# LIA.net
KiCad netlist of a schematic drawn in Altium Designer
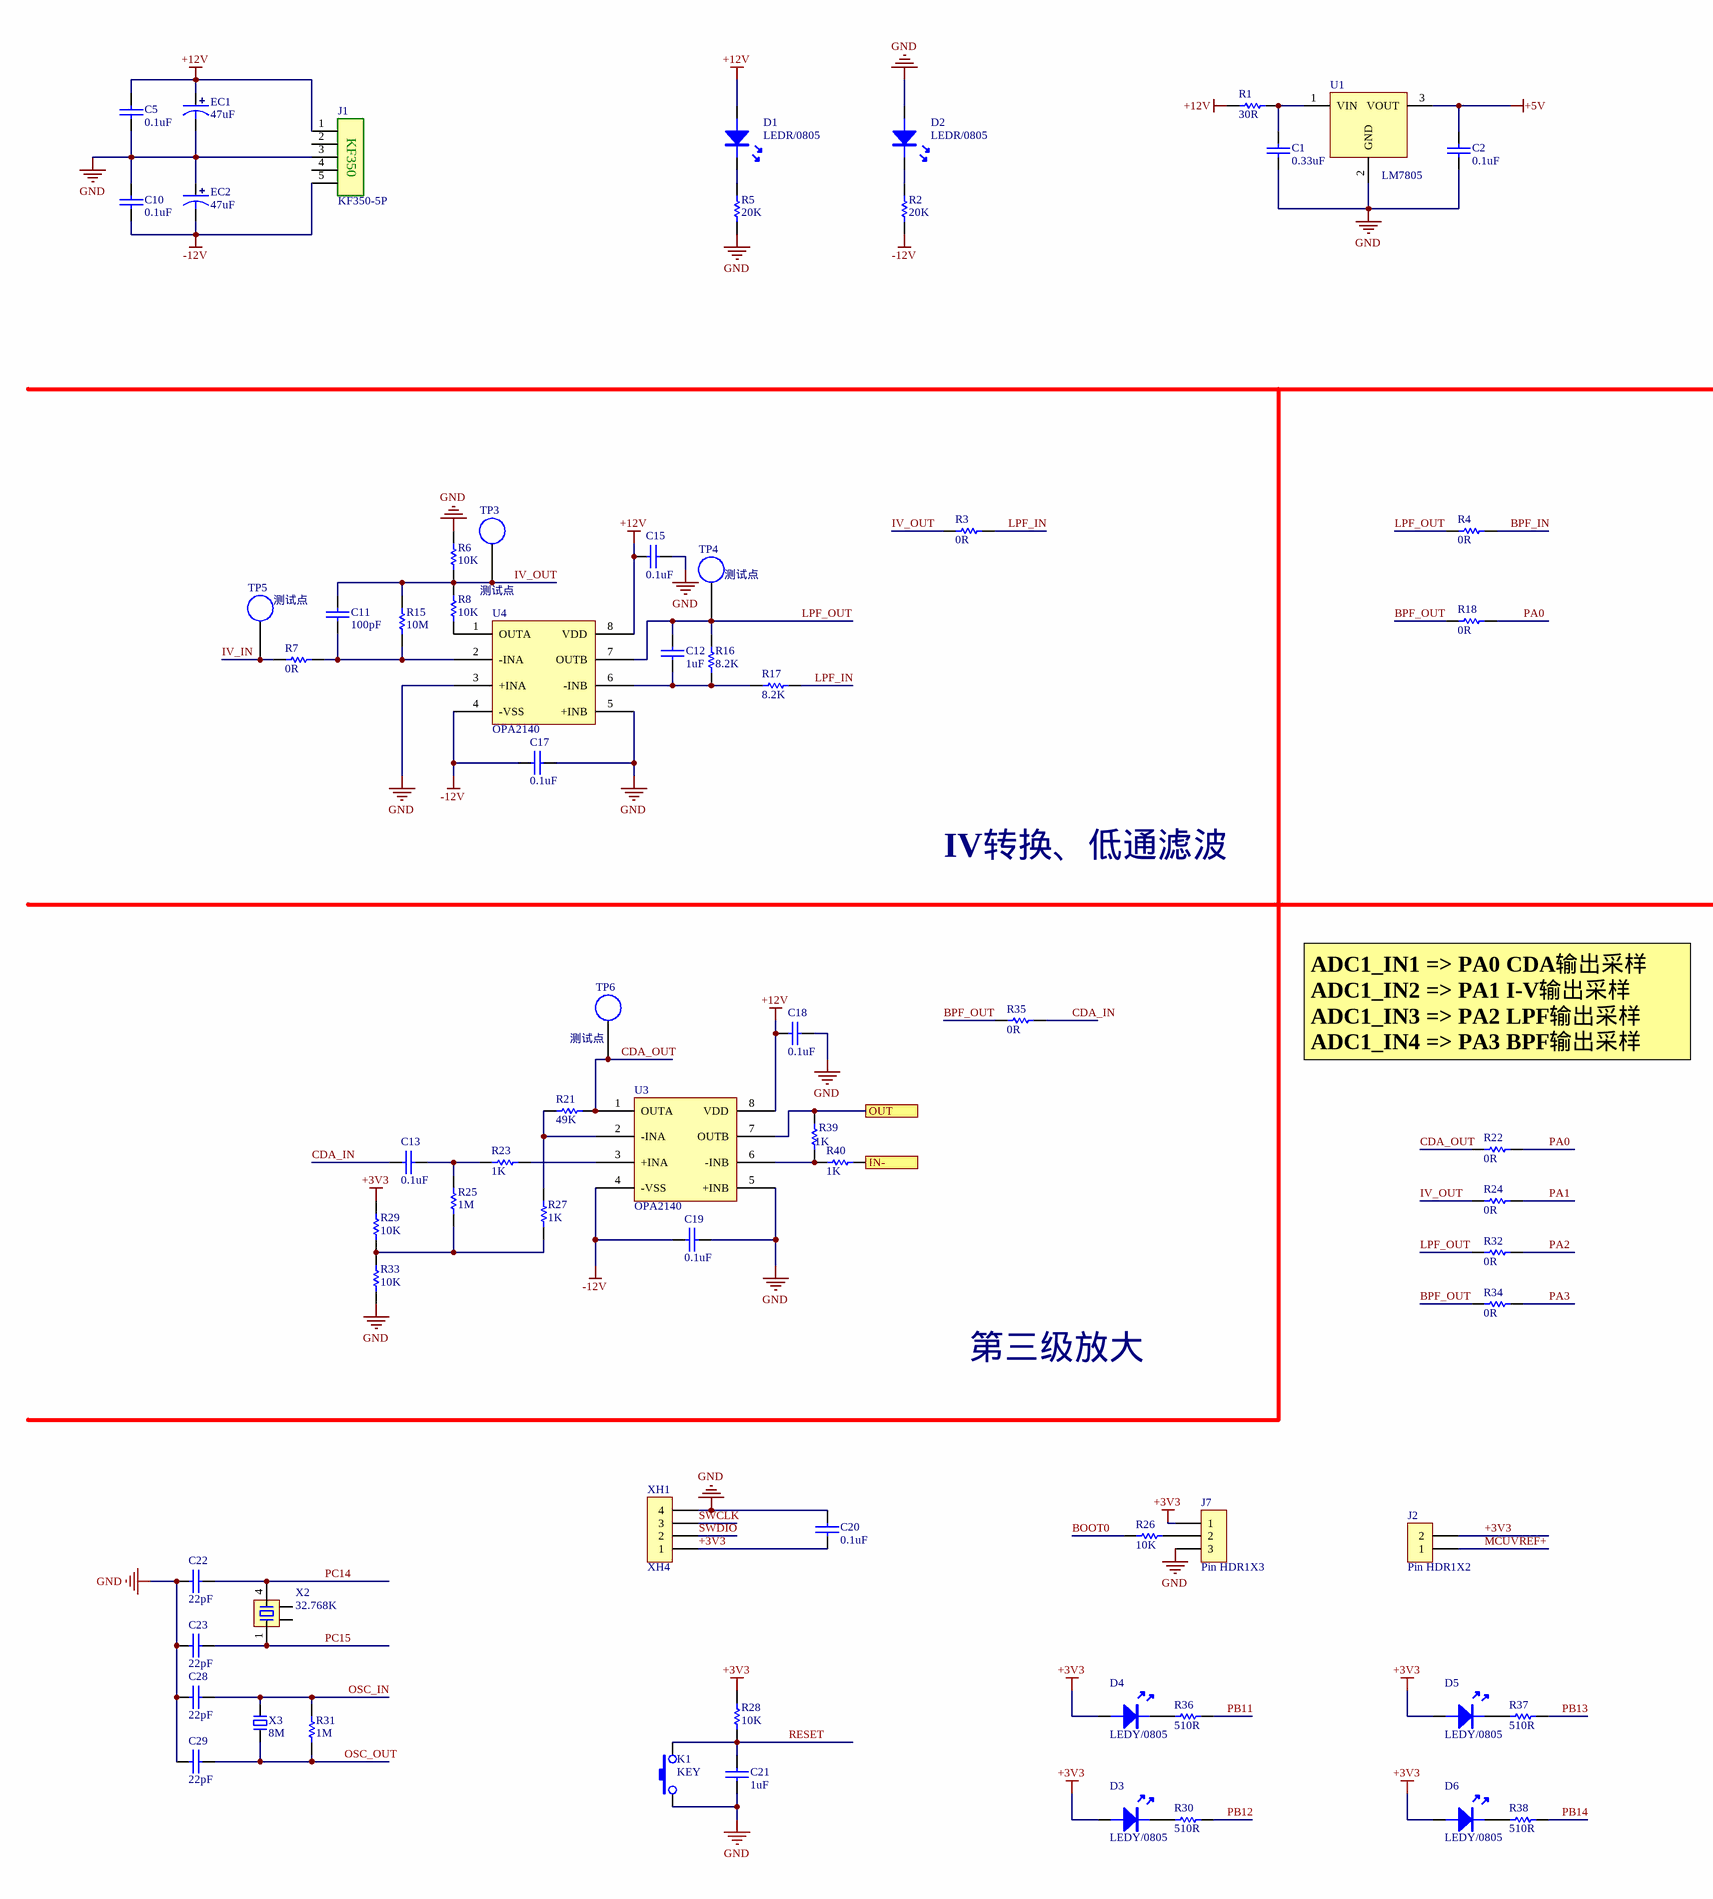
[diagram p0: LIA.SchDoc, left]
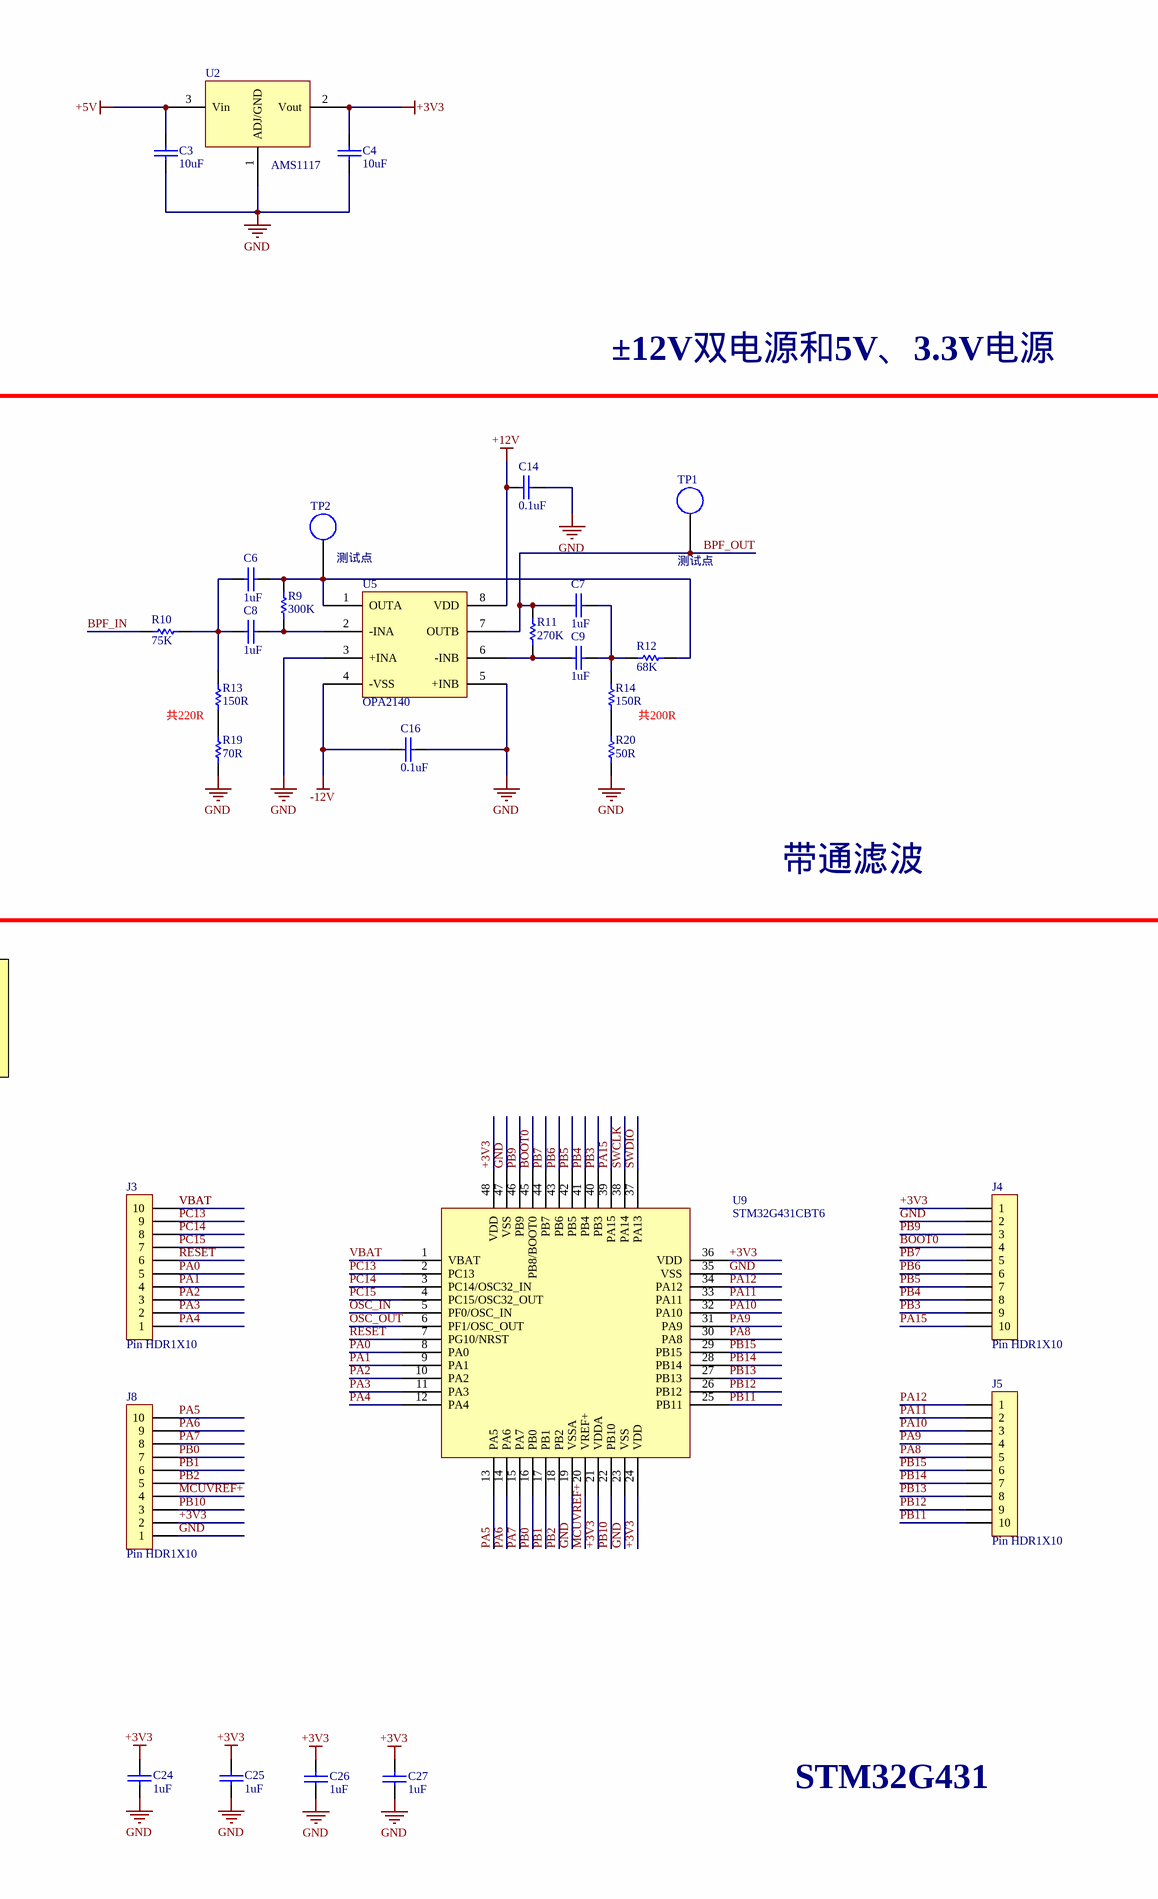
[diagram p1: LIA.SchDoc, right]

(export (version "E")
  (design (tool "Eeschema 10.0.6"))
  (components
    (comp (ref "C1")
      (value "0.33uF")
      (footprint "0603C")
      (description "无极性电容")
      (libsource (lib "电容") (part "CAP"))
    )
    (comp (ref "C2")
      (value "0.1uF")
      (footprint "0603C")
      (description "无极性电容")
      (libsource (lib "电容") (part "CAP"))
    )
    (comp (ref "C3")
      (value "10uF")
      (footprint "0603C")
      (description "无极性电容")
      (libsource (lib "电容") (part "CAP"))
    )
    (comp (ref "C4")
      (value "10uF")
      (footprint "0603C")
      (description "无极性电容")
      (libsource (lib "电容") (part "CAP"))
    )
    (comp (ref "C5")
      (value "0.1uF")
      (footprint "0603C")
      (description "无极性电容")
      (libsource (lib "电容") (part "CAP"))
    )
    (comp (ref "C6")
      (value "1uF")
      (footprint "DIP-7")
      (description "无极性电容")
      (libsource (lib "电容") (part "CAP"))
    )
    (comp (ref "C7")
      (value "1uF")
      (footprint "DIP-7")
      (description "无极性电容")
      (libsource (lib "电容") (part "CAP"))
    )
    (comp (ref "C8")
      (value "1uF")
      (footprint "DIP-7")
      (description "无极性电容")
      (libsource (lib "电容") (part "CAP"))
    )
    (comp (ref "C9")
      (value "1uF")
      (footprint "DIP-7")
      (description "无极性电容")
      (libsource (lib "电容") (part "CAP"))
    )
    (comp (ref "C10")
      (value "0.1uF")
      (footprint "0603C")
      (description "无极性电容")
      (libsource (lib "电容") (part "CAP"))
    )
    (comp (ref "C11")
      (value "100pF")
      (footprint "0603C")
      (description "无极性电容")
      (libsource (lib "电容") (part "CAP"))
    )
    (comp (ref "C12")
      (value "1uF")
      (footprint "0603C")
      (description "无极性电容")
      (libsource (lib "电容") (part "CAP"))
    )
    (comp (ref "C13")
      (value "0.1uF")
      (footprint "0603C")
      (description "无极性电容")
      (libsource (lib "电容") (part "CAP"))
    )
    (comp (ref "C14")
      (value "0.1uF")
      (footprint "0603C")
      (description "无极性电容")
      (libsource (lib "电容") (part "CAP"))
    )
    (comp (ref "C15")
      (value "0.1uF")
      (footprint "0603C")
      (description "无极性电容")
      (libsource (lib "电容") (part "CAP"))
    )
    (comp (ref "C16")
      (value "0.1uF")
      (footprint "0603C")
      (description "无极性电容")
      (libsource (lib "电容") (part "CAP"))
    )
    (comp (ref "C17")
      (value "0.1uF")
      (footprint "0603C")
      (description "无极性电容")
      (libsource (lib "电容") (part "CAP"))
    )
    (comp (ref "C18")
      (value "0.1uF")
      (footprint "0603C")
      (description "无极性电容")
      (libsource (lib "电容") (part "CAP"))
    )
    (comp (ref "C19")
      (value "0.1uF")
      (footprint "0603C")
      (description "无极性电容")
      (libsource (lib "电容") (part "CAP"))
    )
    (comp (ref "C20")
      (value "0.1uF")
      (footprint "0603C")
      (description "无极性电容")
      (libsource (lib "电容") (part "CAP"))
    )
    (comp (ref "C21")
      (value "1uF")
      (footprint "0603C")
      (description "无极性电容")
      (libsource (lib "电容") (part "CAP"))
    )
    (comp (ref "C22")
      (value "22pF")
      (footprint "0603C")
      (description "无极性电容")
      (libsource (lib "电容") (part "CAP"))
    )
    (comp (ref "C23")
      (value "22pF")
      (footprint "0603C")
      (description "无极性电容")
      (libsource (lib "电容") (part "CAP"))
    )
    (comp (ref "C24")
      (value "1uF")
      (footprint "0603C")
      (description "无极性电容")
      (libsource (lib "电容") (part "CAP"))
    )
    (comp (ref "C25")
      (value "1uF")
      (footprint "0603C")
      (description "无极性电容")
      (libsource (lib "电容") (part "CAP"))
    )
    (comp (ref "C26")
      (value "1uF")
      (footprint "0603C")
      (description "无极性电容")
      (libsource (lib "电容") (part "CAP"))
    )
    (comp (ref "C27")
      (value "1uF")
      (footprint "0603C")
      (description "无极性电容")
      (libsource (lib "电容") (part "CAP"))
    )
    (comp (ref "C28")
      (value "22pF")
      (footprint "0603C")
      (description "无极性电容")
      (libsource (lib "电容") (part "CAP"))
    )
    (comp (ref "C29")
      (value "22pF")
      (footprint "0603C")
      (description "无极性电容")
      (libsource (lib "电容") (part "CAP"))
    )
    (comp (ref "D1") (value "LEDR/0805") (footprint "LED-0805R") (libsource (lib "LED") (part "LED")))
    (comp (ref "D2") (value "LEDR/0805") (footprint "LED-0805R") (libsource (lib "LED") (part "LED")))
    (comp (ref "D3") (value "LEDY/0805") (footprint "LED-0805Y") (libsource (lib "LED") (part "LED")))
    (comp (ref "D4") (value "LEDY/0805") (footprint "LED-0805Y") (libsource (lib "LED") (part "LED")))
    (comp (ref "D5") (value "LEDY/0805") (footprint "LED-0805Y") (libsource (lib "LED") (part "LED")))
    (comp (ref "D6") (value "LEDY/0805") (footprint "LED-0805Y") (libsource (lib "LED") (part "LED")))
    (comp (ref "EC1")
      (value "47uF")
      (footprint "SMD-EC5.0X5.3X5.4")
      (description "贴片电解电容")
      (libsource (lib "电容") (part "SMD_ECAP"))
    )
    (comp (ref "EC2")
      (value "47uF")
      (footprint "SMD-EC5.0X5.3X5.4")
      (description "贴片电解电容")
      (libsource (lib "电容") (part "SMD_ECAP"))
    )
    (comp (ref "J1") (value "KF350-5P") (footprint "KF350-5P") (libsource (lib "KF350") (part "KF350-5P")))
    (comp (ref "J2")
      (value "Pin HDR1X2")
      (footprint "Pin HDR1X2/2.54mm-S")
      (libsource (lib "排针") (part "Pin HDR1X2"))
    )
    (comp (ref "J3")
      (value "Pin HDR1X10")
      (footprint "Pin HDR1X10/2.54mm-S")
      (libsource (lib "") (part "Pin HDR1X10_1"))
    )
    (comp (ref "J4")
      (value "Pin HDR1X10")
      (footprint "Pin HDR1X10/2.54mm-S")
      (libsource (lib "排针") (part "Pin HDR1X10"))
    )
    (comp (ref "J5")
      (value "Pin HDR1X10")
      (footprint "Pin HDR1X10/2.54mm-S")
      (libsource (lib "排针") (part "Pin HDR1X10"))
    )
    (comp (ref "J7")
      (value "Pin HDR1X3")
      (footprint "Pin HDR1X3/2.54mm-S")
      (libsource (lib "排针") (part "Pin HDR1X3"))
    )
    (comp (ref "J8")
      (value "Pin HDR1X10")
      (footprint "Pin HDR1X10/2.54mm-S")
      (libsource (lib "") (part "Pin HDR1X10_1"))
    )
    (comp (ref "K1") (value "KEY") (footprint "SMD-3X6X2.5") (libsource (lib "轻触开关") (part "KEY")))
    (comp (ref "R1") (value "30R") (footprint "0603R") (libsource (lib "电阻") (part "RES")))
    (comp (ref "R2") (value "20K") (footprint "0603R") (libsource (lib "电阻") (part "RES")))
    (comp (ref "R3") (value "0R") (footprint "0603R") (libsource (lib "电阻") (part "RES")))
    (comp (ref "R4") (value "0R") (footprint "0603R") (libsource (lib "电阻") (part "RES")))
    (comp (ref "R5") (value "20K") (footprint "0603R") (libsource (lib "电阻") (part "RES")))
    (comp (ref "R6") (value "10K") (footprint "0603R") (libsource (lib "电阻") (part "RES")))
    (comp (ref "R7") (value "0R") (footprint "0603R") (libsource (lib "电阻") (part "RES")))
    (comp (ref "R8") (value "10K") (footprint "0603R") (libsource (lib "电阻") (part "RES")))
    (comp (ref "R9") (value "300K") (footprint "0603R") (libsource (lib "电阻") (part "RES")))
    (comp (ref "R10") (value "75K") (footprint "0603R") (libsource (lib "电阻") (part "RES")))
    (comp (ref "R11") (value "270K") (footprint "0603R") (libsource (lib "电阻") (part "RES")))
    (comp (ref "R12") (value "68K") (footprint "0603R") (libsource (lib "电阻") (part "RES")))
    (comp (ref "R13") (value "150R") (footprint "0603R") (libsource (lib "电阻") (part "RES")))
    (comp (ref "R14") (value "150R") (footprint "0603R") (libsource (lib "电阻") (part "RES")))
    (comp (ref "R15") (value "10M") (footprint "0603R") (libsource (lib "电阻") (part "RES")))
    (comp (ref "R16") (value "8.2K") (footprint "0603R") (libsource (lib "电阻") (part "RES")))
    (comp (ref "R17") (value "8.2K") (footprint "0603R") (libsource (lib "电阻") (part "RES")))
    (comp (ref "R18") (value "0R") (footprint "0603R") (libsource (lib "电阻") (part "RES")))
    (comp (ref "R19") (value "70R") (footprint "0603R") (libsource (lib "电阻") (part "RES")))
    (comp (ref "R20") (value "50R") (footprint "0603R") (libsource (lib "电阻") (part "RES")))
    (comp (ref "R21") (value "49K") (footprint "0603R") (libsource (lib "电阻") (part "RES")))
    (comp (ref "R22") (value "0R") (footprint "0603R") (libsource (lib "电阻") (part "RES")))
    (comp (ref "R23") (value "1K") (footprint "0603R") (libsource (lib "电阻") (part "RES")))
    (comp (ref "R24") (value "0R") (footprint "0603R") (libsource (lib "电阻") (part "RES")))
    (comp (ref "R25") (value "1M") (footprint "0603R") (libsource (lib "电阻") (part "RES")))
    (comp (ref "R26") (value "10K") (footprint "0603R") (libsource (lib "电阻") (part "RES")))
    (comp (ref "R27") (value "1K") (footprint "0603R") (libsource (lib "电阻") (part "RES")))
    (comp (ref "R28") (value "10K") (footprint "0603R") (libsource (lib "电阻") (part "RES")))
    (comp (ref "R29") (value "10K") (footprint "0603R") (libsource (lib "电阻") (part "RES")))
    (comp (ref "R30") (value "510R") (footprint "0603R") (libsource (lib "电阻") (part "RES")))
    (comp (ref "R31") (value "1M") (footprint "0603R") (libsource (lib "电阻") (part "RES")))
    (comp (ref "R32") (value "0R") (footprint "0603R") (libsource (lib "电阻") (part "RES")))
    (comp (ref "R33") (value "10K") (footprint "0603R") (libsource (lib "电阻") (part "RES")))
    (comp (ref "R34") (value "0R") (footprint "0603R") (libsource (lib "电阻") (part "RES")))
    (comp (ref "R35") (value "0R") (footprint "0603R") (libsource (lib "电阻") (part "RES")))
    (comp (ref "R36") (value "510R") (footprint "0603R") (libsource (lib "电阻") (part "RES")))
    (comp (ref "R37") (value "510R") (footprint "0603R") (libsource (lib "电阻") (part "RES")))
    (comp (ref "R38") (value "510R") (footprint "0603R") (libsource (lib "电阻") (part "RES")))
    (comp (ref "R39") (value "1K") (footprint "0603R") (libsource (lib "电阻") (part "RES")))
    (comp (ref "R40") (value "1K") (footprint "0603R") (libsource (lib "电阻") (part "RES")))
    (comp (ref "TP1") (value "测试点") (footprint "TP") (libsource (lib "固定柱和测试点") (part "测试点")))
    (comp (ref "TP2") (value "测试点") (footprint "TP") (libsource (lib "固定柱和测试点") (part "测试点")))
    (comp (ref "TP3") (value "测试点") (footprint "TP") (libsource (lib "固定柱和测试点") (part "测试点")))
    (comp (ref "TP4") (value "测试点") (footprint "TP") (libsource (lib "固定柱和测试点") (part "测试点")))
    (comp (ref "TP5") (value "测试点") (footprint "TP") (libsource (lib "固定柱和测试点") (part "测试点")))
    (comp (ref "TP6") (value "测试点") (footprint "TP") (libsource (lib "固定柱和测试点") (part "测试点")))
    (comp (ref "U1") (value "LM7805") (footprint "TO252") (libsource (lib "电源芯片") (part "LM7805")))
    (comp (ref "U2")
      (value "AMS1117")
      (footprint "SOT223")
      (description "三端稳压芯片")
      (libsource (lib "电源芯片") (part "AMS1117"))
    )
    (comp (ref "U3") (value "OPA2140") (footprint "SOP8") (libsource (lib "未分类IC") (part "NE5532")))
    (comp (ref "U4") (value "OPA2140") (footprint "SOP8") (libsource (lib "未分类IC") (part "NE5532")))
    (comp (ref "U5") (value "OPA2140") (footprint "SOP8") (libsource (lib "未分类IC") (part "NE5532")))
    (comp (ref "U9")
      (value "STM32G431CBT6")
      (footprint "LQFP48 7X7")
      (libsource (lib "STM32系列") (part "STM32G431CBT6"))
    )
    (comp (ref "X2")
      (value "32.768K")
      (footprint "OSC MC-306")
      (description "MC系列4脚晶振")
      (libsource (lib "晶振") (part "XTAL-MC-4P"))
    )
    (comp (ref "X3")
      (value "8M")
      (footprint "OSC HC-49S")
      (description "2脚无源脚晶振")
      (libsource (lib "晶振") (part "XTAL-2P"))
    )
    (comp (ref "XH1") (value "XH4") (footprint "XH4/2.54mm/180") (libsource (lib "XH，VH") (part "XH4")))
  )
  (nets
    (net (code "1") (name "+3V3") (class "Default")
      (node (ref "C20") (pin "1") (pinfunction "1_1") (pintype "passive"))
      (node (ref "C24") (pin "2") (pinfunction "2_2") (pintype "passive"))
      (node (ref "C25") (pin "2") (pinfunction "2_2") (pintype "passive"))
      (node (ref "C26") (pin "2") (pinfunction "2_2") (pintype "passive"))
      (node (ref "C27") (pin "2") (pinfunction "2_2") (pintype "passive"))
      (node (ref "C4") (pin "2") (pinfunction "2_2") (pintype "passive"))
      (node (ref "D3") (pin "A") (pinfunction "A_A") (pintype "passive"))
      (node (ref "D4") (pin "A") (pinfunction "A_A") (pintype "passive"))
      (node (ref "D5") (pin "A") (pinfunction "A_A") (pintype "passive"))
      (node (ref "D6") (pin "A") (pinfunction "A_A") (pintype "passive"))
      (node (ref "J2") (pin "2") (pinfunction "2_2") (pintype "passive"))
      (node (ref "J4") (pin "1") (pinfunction "1_1") (pintype "passive"))
      (node (ref "J7") (pin "1") (pinfunction "1_1") (pintype "passive"))
      (node (ref "J8") (pin "2") (pinfunction "2_2") (pintype "passive"))
      (node (ref "R28") (pin "1") (pinfunction "1_1") (pintype "passive"))
      (node (ref "R29") (pin "2") (pinfunction "2_2") (pintype "passive"))
      (node (ref "U2") (pin "2") (pinfunction "Vout_2") (pintype "passive"))
      (node (ref "U9") (pin "21") (pinfunction "VDDA_21") (pintype "passive"))
      (node (ref "U9") (pin "24") (pinfunction "VDD_24") (pintype "passive"))
      (node (ref "U9") (pin "36") (pinfunction "VDD_36") (pintype "passive"))
      (node (ref "U9") (pin "48") (pinfunction "VDD_48") (pintype "passive"))
      (node (ref "XH1") (pin "1") (pinfunction "1_1") (pintype "passive"))
    )
    (net (code "2") (name "+5V") (class "Default")
      (node (ref "C2") (pin "2") (pinfunction "2_2") (pintype "passive"))
      (node (ref "C3") (pin "2") (pinfunction "2_2") (pintype "passive"))
      (node (ref "U1") (pin "3") (pinfunction "VOUT_3") (pintype "passive"))
      (node (ref "U2") (pin "3") (pinfunction "Vin_3") (pintype "passive"))
    )
    (net (code "3") (name "+12V") (class "Default")
      (node (ref "C14") (pin "1") (pinfunction "1_1") (pintype "passive"))
      (node (ref "C15") (pin "1") (pinfunction "1_1") (pintype "passive"))
      (node (ref "C18") (pin "1") (pinfunction "1_1") (pintype "passive"))
      (node (ref "C5") (pin "2") (pinfunction "2_2") (pintype "passive"))
      (node (ref "D1") (pin "A") (pinfunction "A_A") (pintype "passive"))
      (node (ref "EC1") (pin "1") (pinfunction "1_1") (pintype "passive"))
      (node (ref "J1") (pin "1") (pinfunction "1_1") (pintype "passive"))
      (node (ref "R1") (pin "1") (pinfunction "1_1") (pintype "passive"))
      (node (ref "U3") (pin "8") (pinfunction "VDD_8") (pintype "passive"))
      (node (ref "U4") (pin "8") (pinfunction "VDD_8") (pintype "passive"))
      (node (ref "U5") (pin "8") (pinfunction "VDD_8") (pintype "passive"))
    )
    (net (code "4") (name "-12V") (class "Default")
      (node (ref "C10") (pin "1") (pinfunction "1_1") (pintype "passive"))
      (node (ref "C16") (pin "1") (pinfunction "1_1") (pintype "passive"))
      (node (ref "C17") (pin "1") (pinfunction "1_1") (pintype "passive"))
      (node (ref "C19") (pin "1") (pinfunction "1_1") (pintype "passive"))
      (node (ref "EC2") (pin "2") (pinfunction "2_2") (pintype "passive"))
      (node (ref "J1") (pin "5") (pinfunction "5_5") (pintype "passive"))
      (node (ref "R2") (pin "2") (pinfunction "2_2") (pintype "passive"))
      (node (ref "U3") (pin "4") (pinfunction "-VSS_4") (pintype "passive"))
      (node (ref "U4") (pin "4") (pinfunction "-VSS_4") (pintype "passive"))
      (node (ref "U5") (pin "4") (pinfunction "-VSS_4") (pintype "passive"))
    )
    (net (code "5") (name "/BOOT0") (class "Default")
      (node (ref "J4") (pin "4") (pinfunction "4_4") (pintype "passive"))
      (node (ref "R26") (pin "1") (pinfunction "1_1") (pintype "passive"))
      (node (ref "U9") (pin "45") (pinfunction "PB8/BOOT0_45") (pintype "passive"))
    )
    (net (code "6") (name "/BPF_IN") (class "Default")
      (node (ref "R10") (pin "2") (pinfunction "2_2") (pintype "passive"))
      (node (ref "R4") (pin "2") (pinfunction "2_2") (pintype "passive"))
    )
    (net (code "7") (name "/BPF_OUT") (class "Default")
      (node (ref "C7") (pin "2") (pinfunction "2_2") (pintype "passive"))
      (node (ref "R11") (pin "2") (pinfunction "2_2") (pintype "passive"))
      (node (ref "R18") (pin "1") (pinfunction "1_1") (pintype "passive"))
      (node (ref "R34") (pin "1") (pinfunction "1_1") (pintype "passive"))
      (node (ref "R35") (pin "1") (pinfunction "1_1") (pintype "passive"))
      (node (ref "TP1") (pin "1") (pinfunction "TP_1") (pintype "passive"))
      (node (ref "U5") (pin "7") (pinfunction "OUTB_7") (pintype "passive"))
    )
    (net (code "8") (name "/CDA_IN") (class "Default")
      (node (ref "C13") (pin "1") (pinfunction "1_1") (pintype "passive"))
      (node (ref "R35") (pin "2") (pinfunction "2_2") (pintype "passive"))
    )
    (net (code "9") (name "/CDA_OUT") (class "Default")
      (node (ref "R21") (pin "2") (pinfunction "2_2") (pintype "passive"))
      (node (ref "R22") (pin "1") (pinfunction "1_1") (pintype "passive"))
      (node (ref "TP6") (pin "1") (pinfunction "TP_1") (pintype "passive"))
      (node (ref "U3") (pin "1") (pinfunction "OUTA_1") (pintype "passive"))
    )
    (net (code "10") (name "/IN-") (class "Default")
      (node (ref "R40") (pin "1") (pinfunction "1_1") (pintype "passive"))
    )
    (net (code "11") (name "/IV_IN") (class "Default")
      (node (ref "R7") (pin "2") (pinfunction "2_2") (pintype "passive"))
      (node (ref "TP5") (pin "1") (pinfunction "TP_1") (pintype "passive"))
    )
    (net (code "12") (name "/IV_OUT") (class "Default")
      (node (ref "C11") (pin "1") (pinfunction "1_1") (pintype "passive"))
      (node (ref "R15") (pin "2") (pinfunction "2_2") (pintype "passive"))
      (node (ref "R24") (pin "1") (pinfunction "1_1") (pintype "passive"))
      (node (ref "R3") (pin "1") (pinfunction "1_1") (pintype "passive"))
      (node (ref "R6") (pin "1") (pinfunction "1_1") (pintype "passive"))
      (node (ref "R8") (pin "2") (pinfunction "2_2") (pintype "passive"))
      (node (ref "TP3") (pin "1") (pinfunction "TP_1") (pintype "passive"))
    )
    (net (code "13") (name "/LPF_IN") (class "Default")
      (node (ref "R17") (pin "1") (pinfunction "1_1") (pintype "passive"))
      (node (ref "R3") (pin "2") (pinfunction "2_2") (pintype "passive"))
    )
    (net (code "14") (name "/LPF_OUT") (class "Default")
      (node (ref "C12") (pin "1") (pinfunction "1_1") (pintype "passive"))
      (node (ref "R16") (pin "1") (pinfunction "1_1") (pintype "passive"))
      (node (ref "R32") (pin "1") (pinfunction "1_1") (pintype "passive"))
      (node (ref "R4") (pin "1") (pinfunction "1_1") (pintype "passive"))
      (node (ref "TP4") (pin "1") (pinfunction "TP_1") (pintype "passive"))
      (node (ref "U4") (pin "7") (pinfunction "OUTB_7") (pintype "passive"))
    )
    (net (code "15") (name "/MCUVREF+") (class "Default")
      (node (ref "J2") (pin "1") (pinfunction "1_1") (pintype "passive"))
      (node (ref "J8") (pin "4") (pinfunction "4_4") (pintype "passive"))
      (node (ref "U9") (pin "20") (pinfunction "VREF+_20") (pintype "passive"))
    )
    (net (code "16") (name "/OSC_IN") (class "Default")
      (node (ref "C28") (pin "1") (pinfunction "1_1") (pintype "passive"))
      (node (ref "R31") (pin "2") (pinfunction "2_2") (pintype "passive"))
      (node (ref "U9") (pin "5") (pinfunction "PF0/OSC_IN_5") (pintype "passive"))
      (node (ref "X3") (pin "2") (pinfunction "2_2") (pintype "passive"))
    )
    (net (code "17") (name "/OSC_OUT") (class "Default")
      (node (ref "C29") (pin "1") (pinfunction "1_1") (pintype "passive"))
      (node (ref "R31") (pin "1") (pinfunction "1_1") (pintype "passive"))
      (node (ref "U9") (pin "6") (pinfunction "PF1/OSC_OUT_6") (pintype "passive"))
      (node (ref "X3") (pin "1") (pinfunction "1_1") (pintype "passive"))
    )
    (net (code "18") (name "/OUT") (class "Default")
      (node (ref "R39") (pin "2") (pinfunction "2_2") (pintype "passive"))
      (node (ref "U3") (pin "7") (pinfunction "OUTB_7") (pintype "passive"))
    )
    (net (code "19") (name "/PA0") (class "Default")
      (node (ref "J3") (pin "5") (pinfunction "5_5") (pintype "passive"))
      (node (ref "R18") (pin "2") (pinfunction "2_2") (pintype "passive"))
      (node (ref "R22") (pin "2") (pinfunction "2_2") (pintype "passive"))
      (node (ref "U9") (pin "8") (pinfunction "PA0_8") (pintype "passive"))
    )
    (net (code "20") (name "/PA1") (class "Default")
      (node (ref "J3") (pin "4") (pinfunction "4_4") (pintype "passive"))
      (node (ref "R24") (pin "2") (pinfunction "2_2") (pintype "passive"))
      (node (ref "U9") (pin "9") (pinfunction "PA1_9") (pintype "passive"))
    )
    (net (code "21") (name "/PA2") (class "Default")
      (node (ref "J3") (pin "3") (pinfunction "3_3") (pintype "passive"))
      (node (ref "R32") (pin "2") (pinfunction "2_2") (pintype "passive"))
      (node (ref "U9") (pin "10") (pinfunction "PA2_10") (pintype "passive"))
    )
    (net (code "22") (name "/PA3") (class "Default")
      (node (ref "J3") (pin "2") (pinfunction "2_2") (pintype "passive"))
      (node (ref "R34") (pin "2") (pinfunction "2_2") (pintype "passive"))
      (node (ref "U9") (pin "11") (pinfunction "PA3_11") (pintype "passive"))
    )
    (net (code "23") (name "/PA4") (class "Default")
      (node (ref "J3") (pin "1") (pinfunction "1_1") (pintype "passive"))
      (node (ref "U9") (pin "12") (pinfunction "PA4_12") (pintype "passive"))
    )
    (net (code "24") (name "/PA5") (class "Default")
      (node (ref "J8") (pin "10") (pinfunction "10_10") (pintype "passive"))
      (node (ref "U9") (pin "13") (pinfunction "PA5_13") (pintype "passive"))
    )
    (net (code "25") (name "/PA6") (class "Default")
      (node (ref "J8") (pin "9") (pinfunction "9_9") (pintype "passive"))
      (node (ref "U9") (pin "14") (pinfunction "PA6_14") (pintype "passive"))
    )
    (net (code "26") (name "/PA7") (class "Default")
      (node (ref "J8") (pin "8") (pinfunction "8_8") (pintype "passive"))
      (node (ref "U9") (pin "15") (pinfunction "PA7_15") (pintype "passive"))
    )
    (net (code "27") (name "/PA8") (class "Default")
      (node (ref "J5") (pin "5") (pinfunction "5_5") (pintype "passive"))
      (node (ref "U9") (pin "30") (pinfunction "PA8_30") (pintype "passive"))
    )
    (net (code "28") (name "/PA9") (class "Default")
      (node (ref "J5") (pin "4") (pinfunction "4_4") (pintype "passive"))
      (node (ref "U9") (pin "31") (pinfunction "PA9_31") (pintype "passive"))
    )
    (net (code "29") (name "/PA10") (class "Default")
      (node (ref "J5") (pin "3") (pinfunction "3_3") (pintype "passive"))
      (node (ref "U9") (pin "32") (pinfunction "PA10_32") (pintype "passive"))
    )
    (net (code "30") (name "/PA11") (class "Default")
      (node (ref "J5") (pin "2") (pinfunction "2_2") (pintype "passive"))
      (node (ref "U9") (pin "33") (pinfunction "PA11_33") (pintype "passive"))
    )
    (net (code "31") (name "/PA12") (class "Default")
      (node (ref "J5") (pin "1") (pinfunction "1_1") (pintype "passive"))
      (node (ref "U9") (pin "34") (pinfunction "PA12_34") (pintype "passive"))
    )
    (net (code "32") (name "/PA15") (class "Default")
      (node (ref "J4") (pin "10") (pinfunction "10_10") (pintype "passive"))
      (node (ref "U9") (pin "39") (pinfunction "PA15_39") (pintype "passive"))
    )
    (net (code "33") (name "/PB0") (class "Default")
      (node (ref "J8") (pin "7") (pinfunction "7_7") (pintype "passive"))
      (node (ref "U9") (pin "16") (pinfunction "PB0_16") (pintype "passive"))
    )
    (net (code "34") (name "/PB1") (class "Default")
      (node (ref "J8") (pin "6") (pinfunction "6_6") (pintype "passive"))
      (node (ref "U9") (pin "17") (pinfunction "PB1_17") (pintype "passive"))
    )
    (net (code "35") (name "/PB2") (class "Default")
      (node (ref "J8") (pin "5") (pinfunction "5_5") (pintype "passive"))
      (node (ref "U9") (pin "18") (pinfunction "PB2_18") (pintype "passive"))
    )
    (net (code "36") (name "/PB3") (class "Default")
      (node (ref "J4") (pin "9") (pinfunction "9_9") (pintype "passive"))
      (node (ref "U9") (pin "40") (pinfunction "PB3_40") (pintype "passive"))
    )
    (net (code "37") (name "/PB4") (class "Default")
      (node (ref "J4") (pin "8") (pinfunction "8_8") (pintype "passive"))
      (node (ref "U9") (pin "41") (pinfunction "PB4_41") (pintype "passive"))
    )
    (net (code "38") (name "/PB5") (class "Default")
      (node (ref "J4") (pin "7") (pinfunction "7_7") (pintype "passive"))
      (node (ref "U9") (pin "42") (pinfunction "PB5_42") (pintype "passive"))
    )
    (net (code "39") (name "/PB6") (class "Default")
      (node (ref "J4") (pin "6") (pinfunction "6_6") (pintype "passive"))
      (node (ref "U9") (pin "43") (pinfunction "PB6_43") (pintype "passive"))
    )
    (net (code "40") (name "/PB7") (class "Default")
      (node (ref "J4") (pin "5") (pinfunction "5_5") (pintype "passive"))
      (node (ref "U9") (pin "44") (pinfunction "PB7_44") (pintype "passive"))
    )
    (net (code "41") (name "/PB9") (class "Default")
      (node (ref "J4") (pin "3") (pinfunction "3_3") (pintype "passive"))
      (node (ref "U9") (pin "46") (pinfunction "PB9_46") (pintype "passive"))
    )
    (net (code "42") (name "/PB10") (class "Default")
      (node (ref "J8") (pin "3") (pinfunction "3_3") (pintype "passive"))
      (node (ref "U9") (pin "22") (pinfunction "PB10_22") (pintype "passive"))
    )
    (net (code "43") (name "/PB11") (class "Default")
      (node (ref "J5") (pin "10") (pinfunction "10_10") (pintype "passive"))
      (node (ref "R36") (pin "2") (pinfunction "2_2") (pintype "passive"))
      (node (ref "U9") (pin "25") (pinfunction "PB11_25") (pintype "passive"))
    )
    (net (code "44") (name "/PB12") (class "Default")
      (node (ref "J5") (pin "9") (pinfunction "9_9") (pintype "passive"))
      (node (ref "R30") (pin "2") (pinfunction "2_2") (pintype "passive"))
      (node (ref "U9") (pin "26") (pinfunction "PB12_26") (pintype "passive"))
    )
    (net (code "45") (name "/PB13") (class "Default")
      (node (ref "J5") (pin "8") (pinfunction "8_8") (pintype "passive"))
      (node (ref "R37") (pin "2") (pinfunction "2_2") (pintype "passive"))
      (node (ref "U9") (pin "27") (pinfunction "PB13_27") (pintype "passive"))
    )
    (net (code "46") (name "/PB14") (class "Default")
      (node (ref "J5") (pin "7") (pinfunction "7_7") (pintype "passive"))
      (node (ref "R38") (pin "2") (pinfunction "2_2") (pintype "passive"))
      (node (ref "U9") (pin "28") (pinfunction "PB14_28") (pintype "passive"))
    )
    (net (code "47") (name "/PB15") (class "Default")
      (node (ref "J5") (pin "6") (pinfunction "6_6") (pintype "passive"))
      (node (ref "U9") (pin "29") (pinfunction "PB15_29") (pintype "passive"))
    )
    (net (code "48") (name "/PC13") (class "Default")
      (node (ref "J3") (pin "9") (pinfunction "9_9") (pintype "passive"))
      (node (ref "U9") (pin "2") (pinfunction "PC13_2") (pintype "passive"))
    )
    (net (code "49") (name "/PC14") (class "Default")
      (node (ref "C22") (pin "1") (pinfunction "1_1") (pintype "passive"))
      (node (ref "J3") (pin "8") (pinfunction "8_8") (pintype "passive"))
      (node (ref "U9") (pin "3") (pinfunction "PC14/OSC32_IN_3") (pintype "passive"))
      (node (ref "X2") (pin "4") (pinfunction "4_4") (pintype "passive"))
    )
    (net (code "50") (name "/PC15") (class "Default")
      (node (ref "C23") (pin "1") (pinfunction "1_1") (pintype "passive"))
      (node (ref "J3") (pin "7") (pinfunction "7_7") (pintype "passive"))
      (node (ref "U9") (pin "4") (pinfunction "PC15/OSC32_OUT_4") (pintype "passive"))
      (node (ref "X2") (pin "1") (pinfunction "1_1") (pintype "passive"))
    )
    (net (code "51") (name "/RESET") (class "Default")
      (node (ref "C21") (pin "2") (pinfunction "2_2") (pintype "passive"))
      (node (ref "J3") (pin "6") (pinfunction "6_6") (pintype "passive"))
      (node (ref "K1") (pin "3") (pinfunction "3_3") (pintype "passive"))
      (node (ref "R28") (pin "2") (pinfunction "2_2") (pintype "passive"))
      (node (ref "U9") (pin "7") (pinfunction "PG10/NRST_7") (pintype "passive"))
    )
    (net (code "52") (name "/SWCLK") (class "Default")
      (node (ref "U9") (pin "38") (pinfunction "PA14_38") (pintype "passive"))
      (node (ref "XH1") (pin "3") (pinfunction "3_3") (pintype "passive"))
    )
    (net (code "53") (name "/SWDIO") (class "Default")
      (node (ref "U9") (pin "37") (pinfunction "PA13_37") (pintype "passive"))
      (node (ref "XH1") (pin "2") (pinfunction "2_2") (pintype "passive"))
    )
    (net (code "54") (name "/VBAT") (class "Default")
      (node (ref "J3") (pin "10") (pinfunction "10_10") (pintype "passive"))
      (node (ref "U9") (pin "1") (pinfunction "VBAT_1") (pintype "passive"))
    )
    (net (code "55") (name "GND") (class "Default")
      (node (ref "C1") (pin "1") (pinfunction "1_1") (pintype "passive"))
      (node (ref "C10") (pin "2") (pinfunction "2_2") (pintype "passive"))
      (node (ref "C14") (pin "2") (pinfunction "2_2") (pintype "passive"))
      (node (ref "C15") (pin "2") (pinfunction "2_2") (pintype "passive"))
      (node (ref "C16") (pin "2") (pinfunction "2_2") (pintype "passive"))
      (node (ref "C17") (pin "2") (pinfunction "2_2") (pintype "passive"))
      (node (ref "C18") (pin "2") (pinfunction "2_2") (pintype "passive"))
      (node (ref "C19") (pin "2") (pinfunction "2_2") (pintype "passive"))
      (node (ref "C2") (pin "1") (pinfunction "1_1") (pintype "passive"))
      (node (ref "C20") (pin "2") (pinfunction "2_2") (pintype "passive"))
      (node (ref "C21") (pin "1") (pinfunction "1_1") (pintype "passive"))
      (node (ref "C22") (pin "2") (pinfunction "2_2") (pintype "passive"))
      (node (ref "C23") (pin "2") (pinfunction "2_2") (pintype "passive"))
      (node (ref "C24") (pin "1") (pinfunction "1_1") (pintype "passive"))
      (node (ref "C25") (pin "1") (pinfunction "1_1") (pintype "passive"))
      (node (ref "C26") (pin "1") (pinfunction "1_1") (pintype "passive"))
      (node (ref "C27") (pin "1") (pinfunction "1_1") (pintype "passive"))
      (node (ref "C28") (pin "2") (pinfunction "2_2") (pintype "passive"))
      (node (ref "C29") (pin "2") (pinfunction "2_2") (pintype "passive"))
      (node (ref "C3") (pin "1") (pinfunction "1_1") (pintype "passive"))
      (node (ref "C4") (pin "1") (pinfunction "1_1") (pintype "passive"))
      (node (ref "C5") (pin "1") (pinfunction "1_1") (pintype "passive"))
      (node (ref "D2") (pin "A") (pinfunction "A_A") (pintype "passive"))
      (node (ref "EC1") (pin "2") (pinfunction "2_2") (pintype "passive"))
      (node (ref "EC2") (pin "1") (pinfunction "1_1") (pintype "passive"))
      (node (ref "J1") (pin "3") (pinfunction "3_3") (pintype "passive"))
      (node (ref "J4") (pin "2") (pinfunction "2_2") (pintype "passive"))
      (node (ref "J7") (pin "3") (pinfunction "3_3") (pintype "passive"))
      (node (ref "J8") (pin "1") (pinfunction "1_1") (pintype "passive"))
      (node (ref "K1") (pin "1") (pinfunction "1_1") (pintype "passive"))
      (node (ref "R19") (pin "2") (pinfunction "2_2") (pintype "passive"))
      (node (ref "R20") (pin "2") (pinfunction "2_2") (pintype "passive"))
      (node (ref "R33") (pin "1") (pinfunction "1_1") (pintype "passive"))
      (node (ref "R5") (pin "2") (pinfunction "2_2") (pintype "passive"))
      (node (ref "R6") (pin "2") (pinfunction "2_2") (pintype "passive"))
      (node (ref "U1") (pin "2") (pinfunction "GND_2") (pintype "passive"))
      (node (ref "U2") (pin "1") (pinfunction "ADJ/GND_1") (pintype "passive"))
      (node (ref "U3") (pin "5") (pinfunction "+INB_5") (pintype "passive"))
      (node (ref "U4") (pin "3") (pinfunction "+INA_3") (pintype "passive"))
      (node (ref "U4") (pin "5") (pinfunction "+INB_5") (pintype "passive"))
      (node (ref "U5") (pin "3") (pinfunction "+INA_3") (pintype "passive"))
      (node (ref "U5") (pin "5") (pinfunction "+INB_5") (pintype "passive"))
      (node (ref "U9") (pin "19") (pinfunction "VSSA_19") (pintype "passive"))
      (node (ref "U9") (pin "23") (pinfunction "VSS_23") (pintype "passive"))
      (node (ref "U9") (pin "35") (pinfunction "VSS_35") (pintype "passive"))
      (node (ref "U9") (pin "47") (pinfunction "VSS_47") (pintype "passive"))
      (node (ref "XH1") (pin "4") (pinfunction "4_4") (pintype "passive"))
    )
    (net (code "56") (name "Net-(C6-Pad2)") (class "Default")
      (node (ref "C6") (pin "2") (pinfunction "2_2") (pintype "passive"))
      (node (ref "C8") (pin "1") (pinfunction "1_1") (pintype "passive"))
      (node (ref "R10") (pin "1") (pinfunction "1_1") (pintype "passive"))
      (node (ref "R13") (pin "1") (pinfunction "1_1") (pintype "passive"))
    )
    (net (code "57") (name "Net-(C7-Pad1)") (class "Default")
      (node (ref "C7") (pin "1") (pinfunction "1_1") (pintype "passive"))
      (node (ref "C9") (pin "2") (pinfunction "2_2") (pintype "passive"))
      (node (ref "R12") (pin "2") (pinfunction "2_2") (pintype "passive"))
      (node (ref "R14") (pin "1") (pinfunction "1_1") (pintype "passive"))
    )
    (net (code "58") (name "Net-(C13-Pad2)") (class "Default")
      (node (ref "C13") (pin "2") (pinfunction "2_2") (pintype "passive"))
      (node (ref "R23") (pin "1") (pinfunction "1_1") (pintype "passive"))
      (node (ref "R25") (pin "1") (pinfunction "1_1") (pintype "passive"))
    )
    (net (code "59") (name "Net-(D1-PadK)") (class "Default")
      (node (ref "D1") (pin "K") (pinfunction "K_K") (pintype "passive"))
      (node (ref "R5") (pin "1") (pinfunction "1_1") (pintype "passive"))
    )
    (net (code "60") (name "Net-(D2-PadK)") (class "Default")
      (node (ref "D2") (pin "K") (pinfunction "K_K") (pintype "passive"))
      (node (ref "R2") (pin "1") (pinfunction "1_1") (pintype "passive"))
    )
    (net (code "61") (name "Net-(D3-PadK)") (class "Default")
      (node (ref "D3") (pin "K") (pinfunction "K_K") (pintype "passive"))
      (node (ref "R30") (pin "1") (pinfunction "1_1") (pintype "passive"))
    )
    (net (code "62") (name "Net-(D4-PadK)") (class "Default")
      (node (ref "D4") (pin "K") (pinfunction "K_K") (pintype "passive"))
      (node (ref "R36") (pin "1") (pinfunction "1_1") (pintype "passive"))
    )
    (net (code "63") (name "Net-(D5-PadK)") (class "Default")
      (node (ref "D5") (pin "K") (pinfunction "K_K") (pintype "passive"))
      (node (ref "R37") (pin "1") (pinfunction "1_1") (pintype "passive"))
    )
    (net (code "64") (name "Net-(D6-PadK)") (class "Default")
      (node (ref "D6") (pin "K") (pinfunction "K_K") (pintype "passive"))
      (node (ref "R38") (pin "1") (pinfunction "1_1") (pintype "passive"))
    )
    (net (code "65") (name "Net-(J7-Pad2)") (class "Default")
      (node (ref "J7") (pin "2") (pinfunction "2_2") (pintype "passive"))
      (node (ref "R26") (pin "2") (pinfunction "2_2") (pintype "passive"))
    )
    (net (code "66") (name "Net-(R13-Pad2)") (class "Default")
      (node (ref "R13") (pin "2") (pinfunction "2_2") (pintype "passive"))
      (node (ref "R19") (pin "1") (pinfunction "1_1") (pintype "passive"))
    )
    (net (code "67") (name "Net-(R14-Pad2)") (class "Default")
      (node (ref "R14") (pin "2") (pinfunction "2_2") (pintype "passive"))
      (node (ref "R20") (pin "1") (pinfunction "1_1") (pintype "passive"))
    )
    (net (code "68") (name "Net-(R25-Pad2)") (class "Default")
      (node (ref "R25") (pin "2") (pinfunction "2_2") (pintype "passive"))
      (node (ref "R27") (pin "2") (pinfunction "2_2") (pintype "passive"))
      (node (ref "R29") (pin "1") (pinfunction "1_1") (pintype "passive"))
      (node (ref "R33") (pin "2") (pinfunction "2_2") (pintype "passive"))
    )
    (net (code "69") (name "Net-(TP2-TP)") (class "Default")
      (node (ref "C6") (pin "1") (pinfunction "1_1") (pintype "passive"))
      (node (ref "R12") (pin "1") (pinfunction "1_1") (pintype "passive"))
      (node (ref "R9") (pin "2") (pinfunction "2_2") (pintype "passive"))
      (node (ref "TP2") (pin "1") (pinfunction "TP_1") (pintype "passive"))
      (node (ref "U5") (pin "1") (pinfunction "OUTA_1") (pintype "passive"))
    )
    (net (code "70") (name "Net-(U1-VIN)") (class "Default")
      (node (ref "C1") (pin "2") (pinfunction "2_2") (pintype "passive"))
      (node (ref "R1") (pin "2") (pinfunction "2_2") (pintype "passive"))
      (node (ref "U1") (pin "1") (pinfunction "VIN_1") (pintype "passive"))
    )
    (net (code "71") (name "Net-(U3-+INA)") (class "Default")
      (node (ref "R23") (pin "2") (pinfunction "2_2") (pintype "passive"))
      (node (ref "U3") (pin "3") (pinfunction "+INA_3") (pintype "passive"))
    )
    (net (code "72") (name "Net-(U3--INA)") (class "Default")
      (node (ref "R21") (pin "1") (pinfunction "1_1") (pintype "passive"))
      (node (ref "R27") (pin "1") (pinfunction "1_1") (pintype "passive"))
      (node (ref "U3") (pin "2") (pinfunction "-INA_2") (pintype "passive"))
    )
    (net (code "73") (name "Net-(U3--INB)") (class "Default")
      (node (ref "R39") (pin "1") (pinfunction "1_1") (pintype "passive"))
      (node (ref "R40") (pin "2") (pinfunction "2_2") (pintype "passive"))
      (node (ref "U3") (pin "6") (pinfunction "-INB_6") (pintype "passive"))
    )
    (net (code "74") (name "Net-(U4--INA)") (class "Default")
      (node (ref "C11") (pin "2") (pinfunction "2_2") (pintype "passive"))
      (node (ref "R15") (pin "1") (pinfunction "1_1") (pintype "passive"))
      (node (ref "R7") (pin "1") (pinfunction "1_1") (pintype "passive"))
      (node (ref "U4") (pin "2") (pinfunction "-INA_2") (pintype "passive"))
    )
    (net (code "75") (name "Net-(U4--INB)") (class "Default")
      (node (ref "C12") (pin "2") (pinfunction "2_2") (pintype "passive"))
      (node (ref "R16") (pin "2") (pinfunction "2_2") (pintype "passive"))
      (node (ref "R17") (pin "2") (pinfunction "2_2") (pintype "passive"))
      (node (ref "U4") (pin "6") (pinfunction "-INB_6") (pintype "passive"))
    )
    (net (code "76") (name "Net-(U4-OUTA)") (class "Default")
      (node (ref "R8") (pin "1") (pinfunction "1_1") (pintype "passive"))
      (node (ref "U4") (pin "1") (pinfunction "OUTA_1") (pintype "passive"))
    )
    (net (code "77") (name "Net-(U5--INA)") (class "Default")
      (node (ref "C8") (pin "2") (pinfunction "2_2") (pintype "passive"))
      (node (ref "R9") (pin "1") (pinfunction "1_1") (pintype "passive"))
      (node (ref "U5") (pin "2") (pinfunction "-INA_2") (pintype "passive"))
    )
    (net (code "78") (name "Net-(U5--INB)") (class "Default")
      (node (ref "C9") (pin "1") (pinfunction "1_1") (pintype "passive"))
      (node (ref "R11") (pin "1") (pinfunction "1_1") (pintype "passive"))
      (node (ref "U5") (pin "6") (pinfunction "-INB_6") (pintype "passive"))
    )
    (net (code "79") (name "unconnected-(J1-Pad2)") (class "Default")
      (node (ref "J1") (pin "2") (pinfunction "2_2") (pintype "passive"))
    )
    (net (code "80") (name "unconnected-(J1-Pad4)") (class "Default")
      (node (ref "J1") (pin "4") (pinfunction "4_4") (pintype "passive"))
    )
    (net (code "81") (name "unconnected-(X2-Pad2)") (class "Default")
      (node (ref "X2") (pin "2") (pinfunction "2_2") (pintype "passive"))
    )
    (net (code "82") (name "unconnected-(X2-Pad3)") (class "Default")
      (node (ref "X2") (pin "3") (pinfunction "3_3") (pintype "passive"))
    )
  )
)
